# PCB_Telemetria_2020.net
KiCad netlist of a schematic drawn in EAGLE
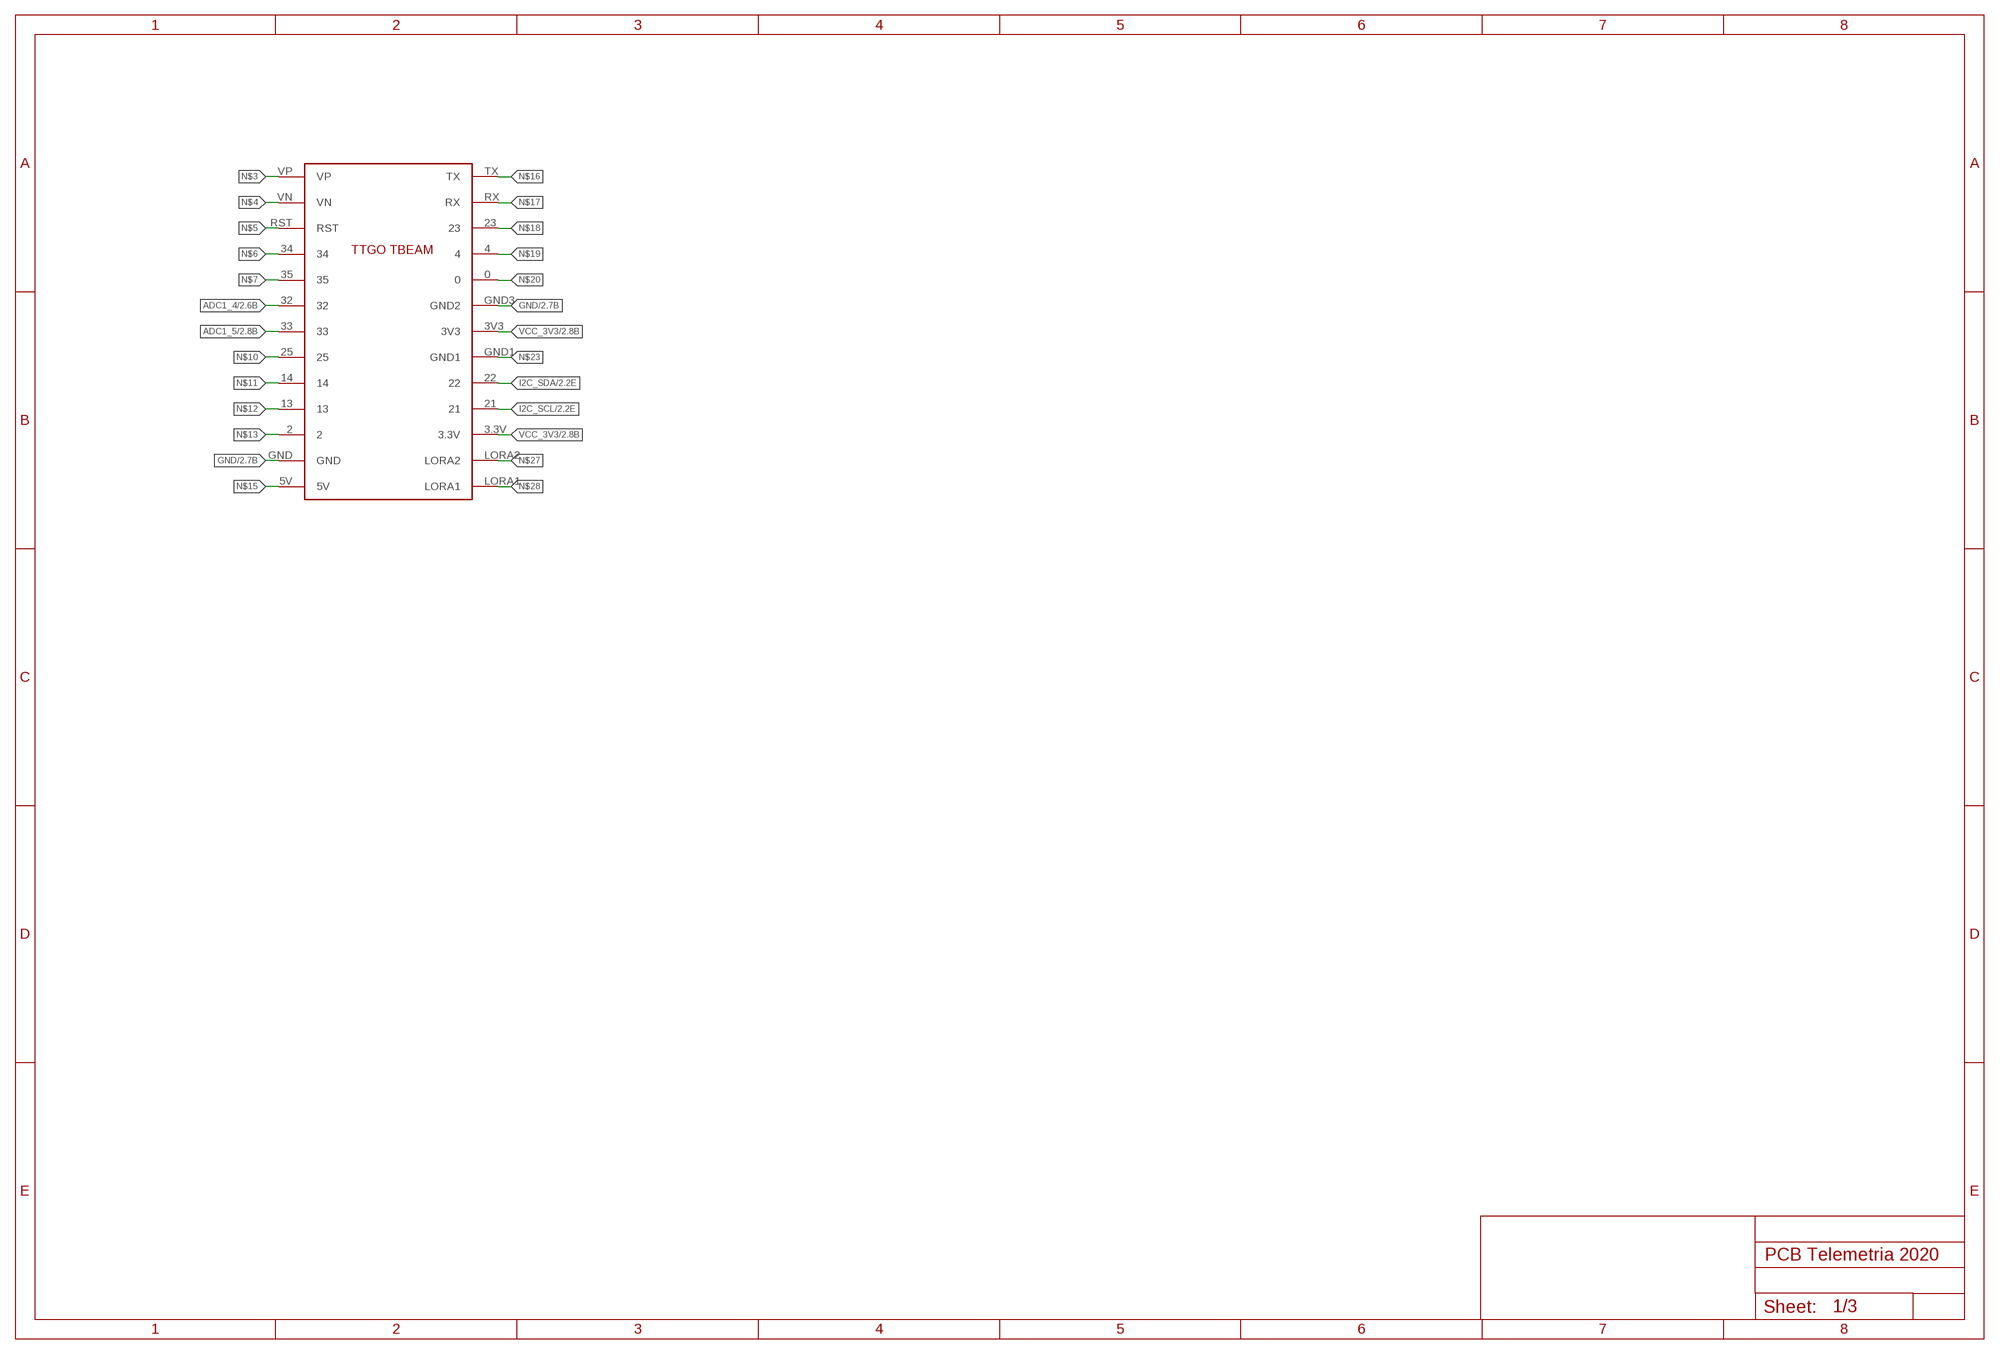
[diagram p0: schematic, sheet 1]
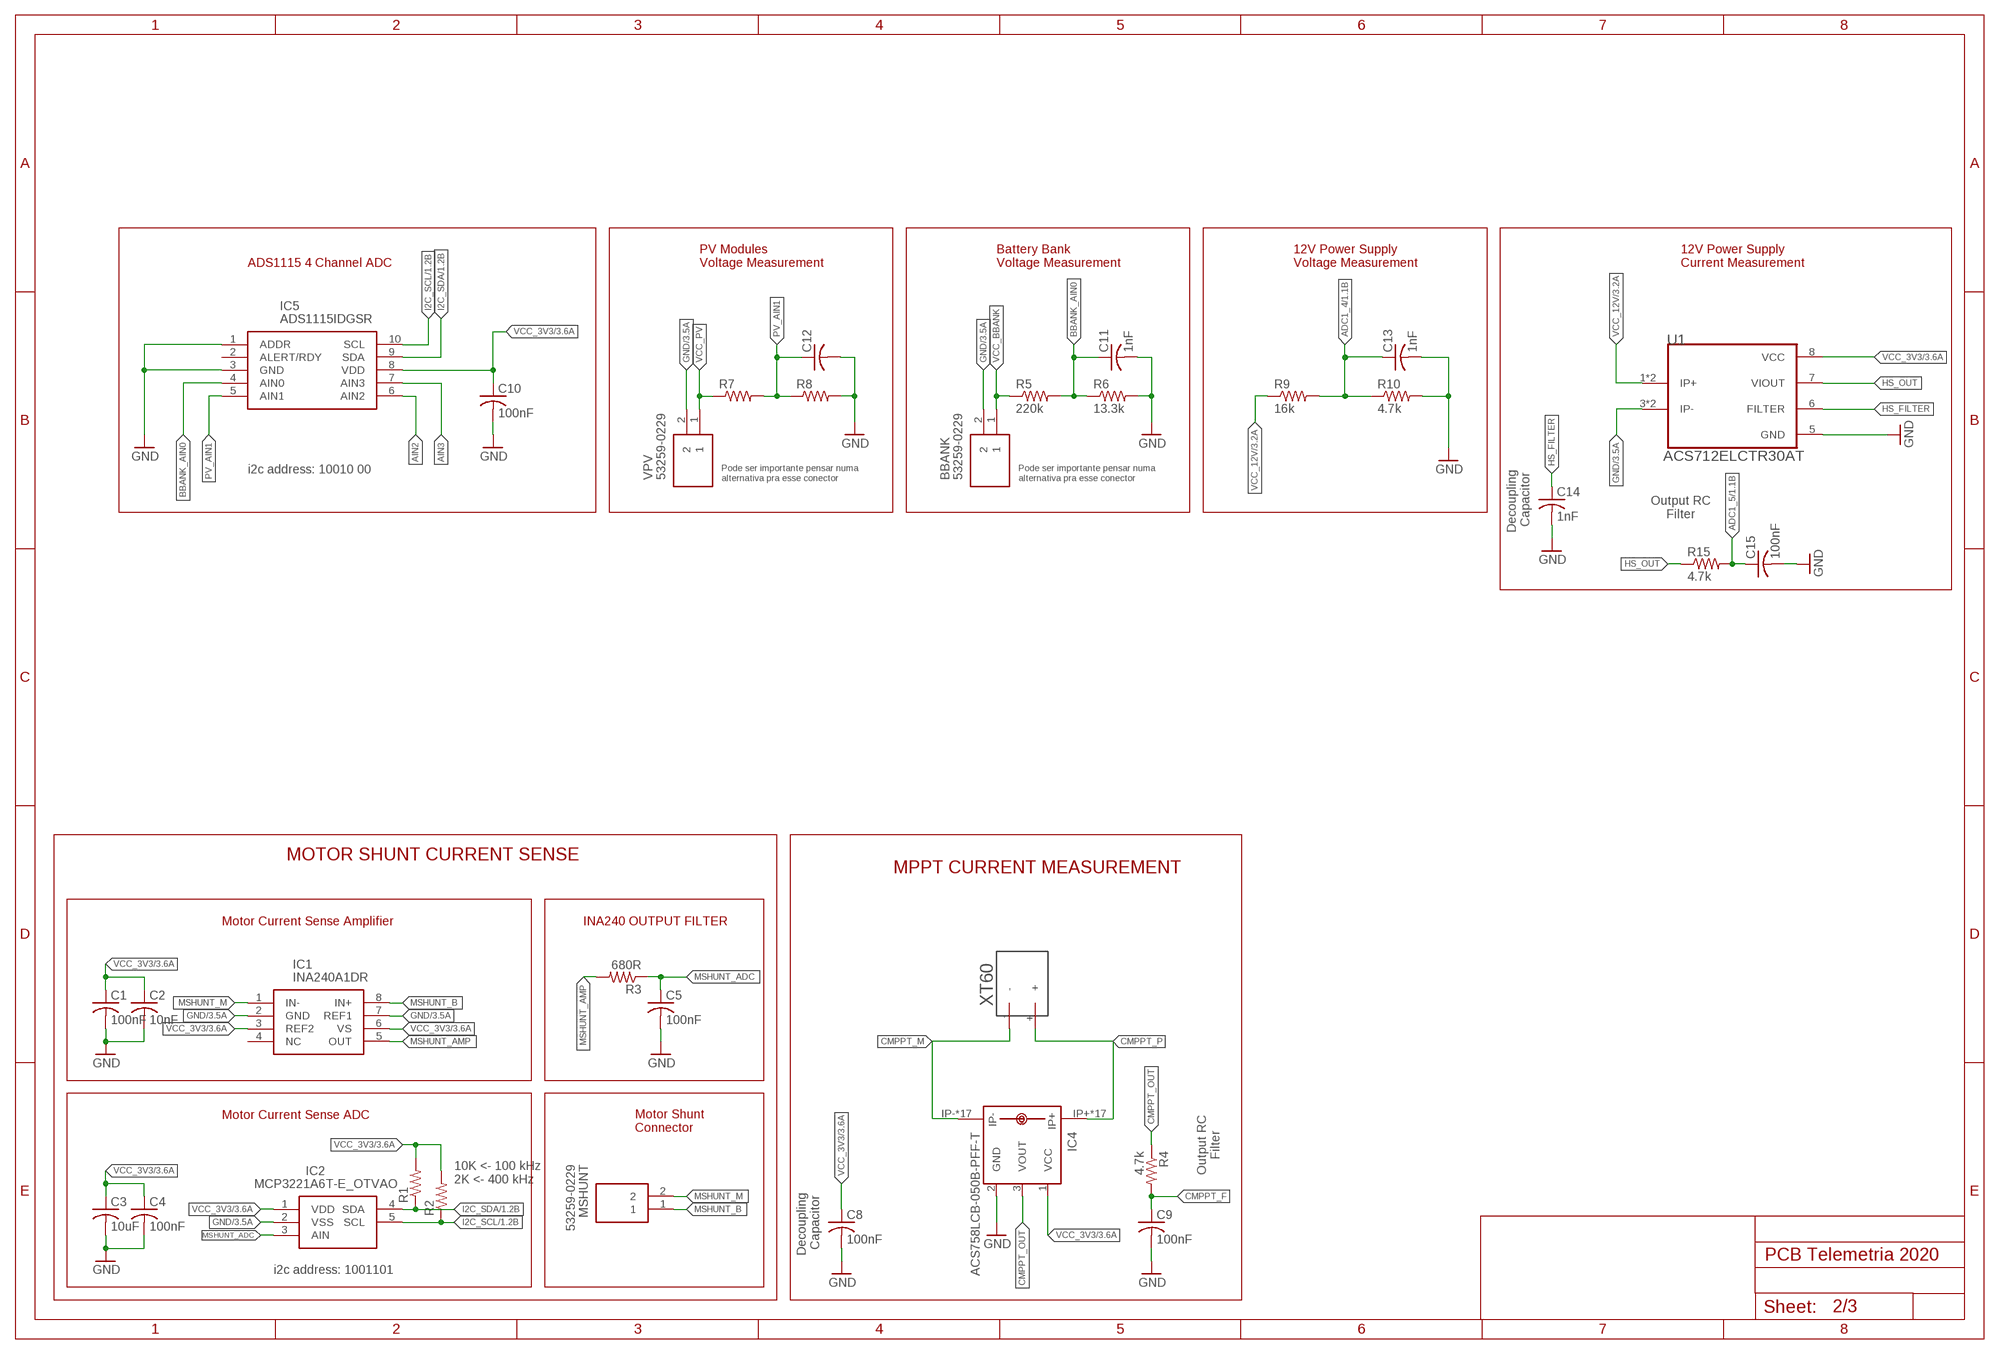
[diagram p1: schematic, sheet 2]
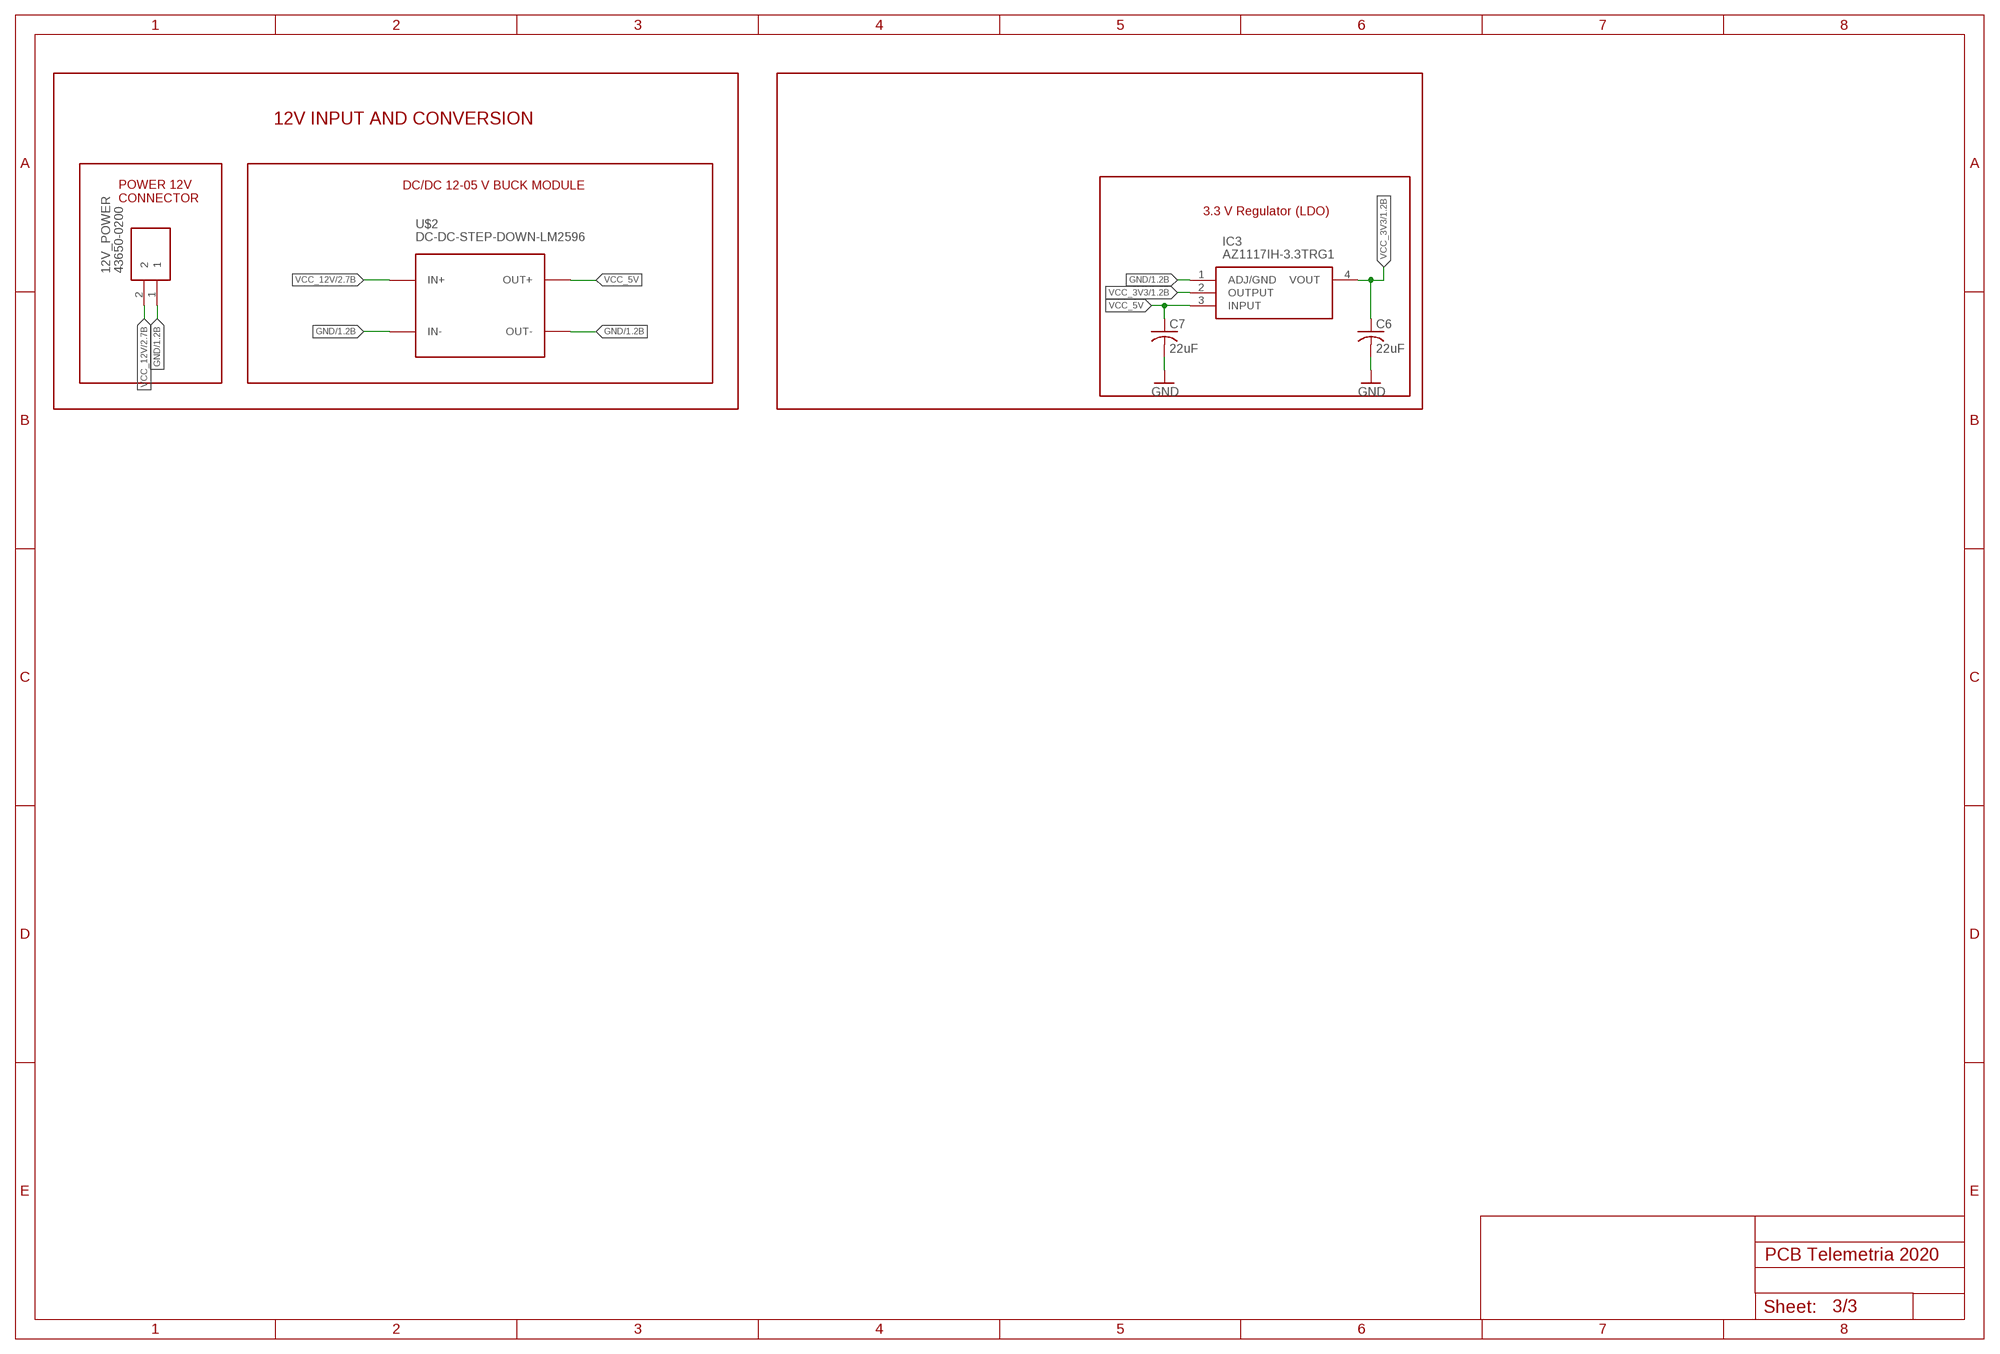
[diagram p2: schematic, sheet 3]

(export (version "E")
  (design (tool "Eeschema 10.0.6"))
  (components
    (comp (ref "12V_POWER")
      (value "43650-0200")
      (footprint "eagle-import:43650-0200")
      (fields (field (name "MOUSER_PART_NUMBER") "538-43650-0200"))
      (libsource (lib "eagle-import") (part "43650-0200"))
    )
    (comp (ref "C6")
      (value "22uF")
      (footprint "eagle-import:C0805")
      (libsource (lib "eagle-import") (part "C-USC0805"))
    )
    (comp (ref "C7")
      (value "22uF")
      (footprint "eagle-import:C0805")
      (libsource (lib "eagle-import") (part "C-USC0805"))
    )
    (comp (ref "IC3")
      (value "AZ1117IH-3.3TRG1")
      (footprint "eagle-import:SOT230P700X170-4N")
      (fields (field (name "MOUSER_PART_NUMBER") "621-AZ1117IH-3.3TRG1"))
      (libsource (lib "eagle-import") (part "AZ1117IH-3.3TRG1"))
    )
    (comp (ref "U$2")
      (value "DC-DC-STEP-DOWN-LM2596")
      (footprint "eagle-import:DC-DC-STEP-DOWN-LM2596")
      (libsource (lib "eagle-import") (part "DC-DC-STEP-DOWN-LM2596"))
    )
    (comp (ref "BBANK")
      (value "53259-0229")
      (footprint "eagle-import:0532590229")
      (fields (field (name "MOUSER_PART_NUMBER") "538-53259-0229"))
      (libsource (lib "eagle-import") (part "53259-0229"))
    )
    (comp (ref "C1")
      (value "100nF")
      (footprint "eagle-import:C0805")
      (libsource (lib "eagle-import") (part "C-USC0805"))
    )
    (comp (ref "C2")
      (value "10nF")
      (footprint "eagle-import:C0805")
      (libsource (lib "eagle-import") (part "C-USC0805"))
    )
    (comp (ref "C3")
      (value "10uF")
      (footprint "eagle-import:C0805")
      (libsource (lib "eagle-import") (part "C-USC0805"))
    )
    (comp (ref "C4")
      (value "100nF")
      (footprint "eagle-import:C0805")
      (libsource (lib "eagle-import") (part "C-USC0805"))
    )
    (comp (ref "C5")
      (value "100nF")
      (footprint "eagle-import:C0805")
      (libsource (lib "eagle-import") (part "C-USC0805"))
    )
    (comp (ref "C8")
      (value "100nF")
      (footprint "eagle-import:C0805")
      (libsource (lib "eagle-import") (part "C-USC0805"))
    )
    (comp (ref "C9")
      (value "100nF")
      (footprint "eagle-import:C0805")
      (libsource (lib "eagle-import") (part "C-USC0805"))
    )
    (comp (ref "C10")
      (value "100nF")
      (footprint "eagle-import:C0805")
      (libsource (lib "eagle-import") (part "C-USC0805"))
    )
    (comp (ref "C11")
      (value "1nF")
      (footprint "eagle-import:C0805")
      (libsource (lib "eagle-import") (part "C-USC0805"))
    )
    (comp (ref "C12")
      (value "C-USC0805")
      (footprint "eagle-import:C0805")
      (libsource (lib "eagle-import") (part "C-USC0805"))
    )
    (comp (ref "C13")
      (value "1nF")
      (footprint "eagle-import:C0805")
      (libsource (lib "eagle-import") (part "C-USC0805"))
    )
    (comp (ref "C14")
      (value "1nF")
      (footprint "eagle-import:C0805")
      (libsource (lib "eagle-import") (part "C-USC0805"))
    )
    (comp (ref "C15")
      (value "100nF")
      (footprint "eagle-import:C0805")
      (libsource (lib "eagle-import") (part "C-USC0805"))
    )
    (comp (ref "IC1")
      (value "INA240A1DR")
      (footprint "eagle-import:SOIC127P600X175-8N")
      (fields (field (name "MOUSER_PART_NUMBER") "595-INA240A1DR"))
      (libsource (lib "eagle-import") (part "INA240A1DR"))
    )
    (comp (ref "IC2")
      (value "MCP3221A6T-E_OTVAO")
      (footprint "eagle-import:SOT95P280X145-5N")
      (fields
        (field (name "MANUFACTURER_PART_NUMBER") "MCP3221A6T-E/OTVAO")
        (field (name "MOUSER_PART_NUMBER") "579-MCP3221A6TEOTVAO")
      )
      (libsource (lib "eagle-import") (part "MCP3221A6T-E_OTVAO"))
    )
    (comp (ref "IC4")
      (value "ACS758LCB-050B-PFF-T")
      (footprint "eagle-import:CB-PFF")
      (libsource (lib "eagle-import") (part "ACS758LCB-050B-PFF-T"))
    )
    (comp (ref "IC5")
      (value "ADS1115IDGSR")
      (footprint "eagle-import:SOP50P490X110-10N")
      (fields (field (name "MOUSER_PART_NUMBER") "595-ADS1115IDGSR"))
      (libsource (lib "eagle-import") (part "ADS1115IDGSR"))
    )
    (comp (ref "MSHUNT")
      (value "53259-0229")
      (footprint "eagle-import:0532590229")
      (fields (field (name "MOUSER_PART_NUMBER") "538-53259-0229"))
      (libsource (lib "eagle-import") (part "53259-0229"))
    )
    (comp (ref "R1")
      (value "R-US_R0805")
      (footprint "eagle-import:R0805")
      (libsource (lib "eagle-import") (part "R-US_R0805"))
    )
    (comp (ref "R2")
      (value "R-US_R0805")
      (footprint "eagle-import:R0805")
      (libsource (lib "eagle-import") (part "R-US_R0805"))
    )
    (comp (ref "R3")
      (value "680R")
      (footprint "eagle-import:R0805")
      (libsource (lib "eagle-import") (part "R-US_R0805"))
    )
    (comp (ref "R4")
      (value "4.7k")
      (footprint "eagle-import:R0805")
      (libsource (lib "eagle-import") (part "R-US_R0805"))
    )
    (comp (ref "R5")
      (value "220k")
      (footprint "eagle-import:R0805")
      (libsource (lib "eagle-import") (part "R-US_R0805"))
    )
    (comp (ref "R6")
      (value "13.3k")
      (footprint "eagle-import:R0805")
      (libsource (lib "eagle-import") (part "R-US_R0805"))
    )
    (comp (ref "R7")
      (value "R-US_R0805")
      (footprint "eagle-import:R0805")
      (libsource (lib "eagle-import") (part "R-US_R0805"))
    )
    (comp (ref "R8")
      (value "R-US_R0805")
      (footprint "eagle-import:R0805")
      (libsource (lib "eagle-import") (part "R-US_R0805"))
    )
    (comp (ref "R9")
      (value "16k")
      (footprint "eagle-import:R0805")
      (libsource (lib "eagle-import") (part "R-US_R0805"))
    )
    (comp (ref "R10")
      (value "4.7k")
      (footprint "eagle-import:R0805")
      (libsource (lib "eagle-import") (part "R-US_R0805"))
    )
    (comp (ref "R15")
      (value "4.7k")
      (footprint "eagle-import:R0805")
      (libsource (lib "eagle-import") (part "R-US_R0805"))
    )
    (comp (ref "U$3")
      (value "XT60")
      (footprint "eagle-import:XT60")
      (libsource (lib "eagle-import") (part "XT60"))
    )
    (comp (ref "U1")
      (value "ACS712ELCTR30AT")
      (footprint "eagle-import:SOIC127P600X175-8N")
      (fields (field (name "MF") "Allegro") (field (name "MP") "ACS712ELCTR-30A-T"))
      (libsource (lib "eagle-import") (part "ACS712ELCTR30AT"))
    )
    (comp (ref "VPV")
      (value "53259-0229")
      (footprint "eagle-import:0532590229")
      (fields (field (name "MOUSER_PART_NUMBER") "538-53259-0229"))
      (libsource (lib "eagle-import") (part "53259-0229"))
    )
    (comp (ref "U$1")
      (value "TTGOBEAM")
      (footprint "eagle-import:TTGOBEAM")
      (libsource (lib "eagle-import") (part "TTGOBEAM"))
    )
  )
  (nets
    (net (code "1") (name "ADC1_4") (class "Default")
      (node (ref "C13") (pin "1") (pinfunction "1_1") (pintype "passive"))
      (node (ref "R10") (pin "1") (pinfunction "1_1") (pintype "passive"))
      (node (ref "R9") (pin "2") (pinfunction "2_2") (pintype "passive"))
      (node (ref "U$1") (pin "32") (pinfunction "32_32") (pintype "bidirectional"))
    )
    (net (code "2") (name "ADC1_5") (class "Default")
      (node (ref "C15") (pin "1") (pinfunction "1_1") (pintype "passive"))
      (node (ref "R15") (pin "2") (pinfunction "2_2") (pintype "passive"))
      (node (ref "U$1") (pin "33") (pinfunction "33_33") (pintype "bidirectional"))
    )
    (net (code "3") (name "AIN2") (class "Default")
      (node (ref "IC5") (pin "6") (pinfunction "AIN2_6") (pintype "bidirectional"))
    )
    (net (code "4") (name "AIN3") (class "Default")
      (node (ref "IC5") (pin "7") (pinfunction "AIN3_7") (pintype "bidirectional"))
    )
    (net (code "5") (name "BBANK_AIN0") (class "Default")
      (node (ref "C11") (pin "1") (pinfunction "1_1") (pintype "passive"))
      (node (ref "IC5") (pin "4") (pinfunction "AIN0_4") (pintype "bidirectional"))
      (node (ref "R5") (pin "2") (pinfunction "2_2") (pintype "passive"))
      (node (ref "R6") (pin "1") (pinfunction "1_1") (pintype "passive"))
    )
    (net (code "6") (name "CMPPT_F") (class "Default")
      (node (ref "C9") (pin "1") (pinfunction "1_1") (pintype "passive"))
      (node (ref "R4") (pin "2") (pinfunction "2_2") (pintype "passive"))
    )
    (net (code "7") (name "CMPPT_M") (class "Default")
      (node (ref "IC4") (pin "IP-") (pinfunction "IP-_IP-") (pintype "passive"))
      (node (ref "IC4") (pin "IP-@10") (pinfunction "IP-_IP-@10") (pintype "passive"))
      (node (ref "IC4") (pin "IP-@11") (pinfunction "IP-_IP-@11") (pintype "passive"))
      (node (ref "IC4") (pin "IP-@12") (pinfunction "IP-_IP-@12") (pintype "passive"))
      (node (ref "IC4") (pin "IP-@13") (pinfunction "IP-_IP-@13") (pintype "passive"))
      (node (ref "IC4") (pin "IP-@14") (pinfunction "IP-_IP-@14") (pintype "passive"))
      (node (ref "IC4") (pin "IP-@15") (pinfunction "IP-_IP-@15") (pintype "passive"))
      (node (ref "IC4") (pin "IP-@16") (pinfunction "IP-_IP-@16") (pintype "passive"))
      (node (ref "IC4") (pin "IP-@17") (pinfunction "IP-_IP-@17") (pintype "passive"))
      (node (ref "IC4") (pin "IP-@2") (pinfunction "IP-_IP-@2") (pintype "passive"))
      (node (ref "IC4") (pin "IP-@3") (pinfunction "IP-_IP-@3") (pintype "passive"))
      (node (ref "IC4") (pin "IP-@4") (pinfunction "IP-_IP-@4") (pintype "passive"))
      (node (ref "IC4") (pin "IP-@5") (pinfunction "IP-_IP-@5") (pintype "passive"))
      (node (ref "IC4") (pin "IP-@6") (pinfunction "IP-_IP-@6") (pintype "passive"))
      (node (ref "IC4") (pin "IP-@7") (pinfunction "IP-_IP-@7") (pintype "passive"))
      (node (ref "IC4") (pin "IP-@8") (pinfunction "IP-_IP-@8") (pintype "passive"))
      (node (ref "IC4") (pin "IP-@9") (pinfunction "IP-_IP-@9") (pintype "passive"))
      (node (ref "U$3") (pin "-") (pinfunction "-_-") (pintype "bidirectional"))
    )
    (net (code "8") (name "CMPPT_OUT") (class "Default")
      (node (ref "IC4") (pin "3") (pinfunction "VOUT_3") (pintype "output"))
      (node (ref "R4") (pin "1") (pinfunction "1_1") (pintype "passive"))
    )
    (net (code "9") (name "CMPPT_P") (class "Default")
      (node (ref "IC4") (pin "IP+") (pinfunction "IP+_IP+") (pintype "passive"))
      (node (ref "IC4") (pin "IP+@10") (pinfunction "IP+_IP+@10") (pintype "passive"))
      (node (ref "IC4") (pin "IP+@11") (pinfunction "IP+_IP+@11") (pintype "passive"))
      (node (ref "IC4") (pin "IP+@12") (pinfunction "IP+_IP+@12") (pintype "passive"))
      (node (ref "IC4") (pin "IP+@13") (pinfunction "IP+_IP+@13") (pintype "passive"))
      (node (ref "IC4") (pin "IP+@14") (pinfunction "IP+_IP+@14") (pintype "passive"))
      (node (ref "IC4") (pin "IP+@15") (pinfunction "IP+_IP+@15") (pintype "passive"))
      (node (ref "IC4") (pin "IP+@16") (pinfunction "IP+_IP+@16") (pintype "passive"))
      (node (ref "IC4") (pin "IP+@17") (pinfunction "IP+_IP+@17") (pintype "passive"))
      (node (ref "IC4") (pin "IP+@2") (pinfunction "IP+_IP+@2") (pintype "passive"))
      (node (ref "IC4") (pin "IP+@3") (pinfunction "IP+_IP+@3") (pintype "passive"))
      (node (ref "IC4") (pin "IP+@4") (pinfunction "IP+_IP+@4") (pintype "passive"))
      (node (ref "IC4") (pin "IP+@5") (pinfunction "IP+_IP+@5") (pintype "passive"))
      (node (ref "IC4") (pin "IP+@6") (pinfunction "IP+_IP+@6") (pintype "passive"))
      (node (ref "IC4") (pin "IP+@7") (pinfunction "IP+_IP+@7") (pintype "passive"))
      (node (ref "IC4") (pin "IP+@8") (pinfunction "IP+_IP+@8") (pintype "passive"))
      (node (ref "IC4") (pin "IP+@9") (pinfunction "IP+_IP+@9") (pintype "passive"))
      (node (ref "U$3") (pin "+") (pinfunction "+_+") (pintype "bidirectional"))
    )
    (net (code "10") (name "GND") (class "Default")
      (node (ref "12V_POWER") (pin "1") (pinfunction "1_1") (pintype "bidirectional"))
      (node (ref "BBANK") (pin "2") (pinfunction "2_2") (pintype "bidirectional"))
      (node (ref "C1") (pin "2") (pinfunction "2_2") (pintype "passive"))
      (node (ref "C10") (pin "2") (pinfunction "2_2") (pintype "passive"))
      (node (ref "C11") (pin "2") (pinfunction "2_2") (pintype "passive"))
      (node (ref "C12") (pin "2") (pinfunction "2_2") (pintype "passive"))
      (node (ref "C13") (pin "2") (pinfunction "2_2") (pintype "passive"))
      (node (ref "C14") (pin "2") (pinfunction "2_2") (pintype "passive"))
      (node (ref "C15") (pin "2") (pinfunction "2_2") (pintype "passive"))
      (node (ref "C2") (pin "2") (pinfunction "2_2") (pintype "passive"))
      (node (ref "C3") (pin "2") (pinfunction "2_2") (pintype "passive"))
      (node (ref "C4") (pin "2") (pinfunction "2_2") (pintype "passive"))
      (node (ref "C5") (pin "2") (pinfunction "2_2") (pintype "passive"))
      (node (ref "C6") (pin "2") (pinfunction "2_2") (pintype "passive"))
      (node (ref "C7") (pin "2") (pinfunction "2_2") (pintype "passive"))
      (node (ref "C8") (pin "2") (pinfunction "2_2") (pintype "passive"))
      (node (ref "C9") (pin "2") (pinfunction "2_2") (pintype "passive"))
      (node (ref "IC1") (pin "2") (pinfunction "GND_2") (pintype "bidirectional"))
      (node (ref "IC1") (pin "7") (pinfunction "REF1_7") (pintype "bidirectional"))
      (node (ref "IC2") (pin "2") (pinfunction "VSS_2") (pintype "bidirectional"))
      (node (ref "IC3") (pin "1") (pinfunction "ADJ/GND_1") (pintype "bidirectional"))
      (node (ref "IC4") (pin "2") (pinfunction "GND_2") (pintype "power_in"))
      (node (ref "IC5") (pin "1") (pinfunction "ADDR_1") (pintype "bidirectional"))
      (node (ref "IC5") (pin "3") (pinfunction "GND_3") (pintype "bidirectional"))
      (node (ref "R10") (pin "2") (pinfunction "2_2") (pintype "passive"))
      (node (ref "R6") (pin "2") (pinfunction "2_2") (pintype "passive"))
      (node (ref "R8") (pin "2") (pinfunction "2_2") (pintype "passive"))
      (node (ref "U$1") (pin "GND") (pinfunction "GND_GND") (pintype "bidirectional"))
      (node (ref "U$1") (pin "GND3") (pinfunction "GND2_GND3") (pintype "bidirectional"))
      (node (ref "U$2") (pin "IN-") (pinfunction "IN-_IN-") (pintype "bidirectional"))
      (node (ref "U$2") (pin "OUT-") (pinfunction "OUT-_OUT-") (pintype "bidirectional"))
      (node (ref "U1") (pin "3") (pinfunction "IP-_3") (pintype "input"))
      (node (ref "U1") (pin "4") (pinfunction "IP-_4") (pintype "input"))
      (node (ref "U1") (pin "5") (pinfunction "GND_5") (pintype "power_in"))
      (node (ref "VPV") (pin "2") (pinfunction "2_2") (pintype "bidirectional"))
    )
    (net (code "11") (name "HS_FILTER") (class "Default")
      (node (ref "C14") (pin "1") (pinfunction "1_1") (pintype "passive"))
      (node (ref "U1") (pin "6") (pinfunction "FILTER_6") (pintype "passive"))
    )
    (net (code "12") (name "HS_OUT") (class "Default")
      (node (ref "R15") (pin "1") (pinfunction "1_1") (pintype "passive"))
      (node (ref "U1") (pin "7") (pinfunction "VIOUT_7") (pintype "output"))
    )
    (net (code "13") (name "I2C_SCL") (class "Default")
      (node (ref "IC2") (pin "5") (pinfunction "SCL_5") (pintype "bidirectional"))
      (node (ref "IC5") (pin "10") (pinfunction "SCL_10") (pintype "bidirectional"))
      (node (ref "R2") (pin "1") (pinfunction "1_1") (pintype "passive"))
      (node (ref "U$1") (pin "21") (pinfunction "21_21") (pintype "bidirectional"))
    )
    (net (code "14") (name "I2C_SDA") (class "Default")
      (node (ref "IC2") (pin "4") (pinfunction "SDA_4") (pintype "bidirectional"))
      (node (ref "IC5") (pin "9") (pinfunction "SDA_9") (pintype "bidirectional"))
      (node (ref "R1") (pin "1") (pinfunction "1_1") (pintype "passive"))
      (node (ref "U$1") (pin "22") (pinfunction "22_22") (pintype "bidirectional"))
    )
    (net (code "15") (name "MSHUNT_ADC") (class "Default")
      (node (ref "C5") (pin "1") (pinfunction "1_1") (pintype "passive"))
      (node (ref "IC2") (pin "3") (pinfunction "AIN_3") (pintype "bidirectional"))
      (node (ref "R3") (pin "1") (pinfunction "1_1") (pintype "passive"))
    )
    (net (code "16") (name "MSHUNT_AMP") (class "Default")
      (node (ref "IC1") (pin "5") (pinfunction "OUT_5") (pintype "bidirectional"))
      (node (ref "R3") (pin "2") (pinfunction "2_2") (pintype "passive"))
    )
    (net (code "17") (name "MSHUNT_B") (class "Default")
      (node (ref "IC1") (pin "8") (pinfunction "IN+_8") (pintype "bidirectional"))
      (node (ref "MSHUNT") (pin "1") (pinfunction "1_1") (pintype "bidirectional"))
    )
    (net (code "18") (name "MSHUNT_M") (class "Default")
      (node (ref "IC1") (pin "1") (pinfunction "IN-_1") (pintype "bidirectional"))
      (node (ref "MSHUNT") (pin "2") (pinfunction "2_2") (pintype "bidirectional"))
    )
    (net (code "19") (name "N$3") (class "Default")
      (node (ref "U$1") (pin "VP") (pinfunction "VP_VP") (pintype "bidirectional"))
    )
    (net (code "20") (name "N$4") (class "Default")
      (node (ref "U$1") (pin "VN") (pinfunction "VN_VN") (pintype "bidirectional"))
    )
    (net (code "21") (name "N$5") (class "Default")
      (node (ref "U$1") (pin "RST") (pinfunction "RST_RST") (pintype "bidirectional"))
    )
    (net (code "22") (name "N$6") (class "Default")
      (node (ref "U$1") (pin "34") (pinfunction "34_34") (pintype "bidirectional"))
    )
    (net (code "23") (name "N$7") (class "Default")
      (node (ref "U$1") (pin "35") (pinfunction "35_35") (pintype "bidirectional"))
    )
    (net (code "24") (name "N$10") (class "Default")
      (node (ref "U$1") (pin "25") (pinfunction "25_25") (pintype "bidirectional"))
    )
    (net (code "25") (name "N$11") (class "Default")
      (node (ref "U$1") (pin "14") (pinfunction "14_14") (pintype "bidirectional"))
    )
    (net (code "26") (name "N$12") (class "Default")
      (node (ref "U$1") (pin "13") (pinfunction "13_13") (pintype "bidirectional"))
    )
    (net (code "27") (name "N$13") (class "Default")
      (node (ref "U$1") (pin "2") (pinfunction "2_2") (pintype "bidirectional"))
    )
    (net (code "28") (name "N$15") (class "Default")
      (node (ref "U$1") (pin "5V") (pinfunction "5V_5V") (pintype "bidirectional"))
    )
    (net (code "29") (name "N$16") (class "Default")
      (node (ref "U$1") (pin "TX") (pinfunction "TX_TX") (pintype "bidirectional"))
    )
    (net (code "30") (name "N$17") (class "Default")
      (node (ref "U$1") (pin "RX") (pinfunction "RX_RX") (pintype "bidirectional"))
    )
    (net (code "31") (name "N$18") (class "Default")
      (node (ref "U$1") (pin "23") (pinfunction "23_23") (pintype "bidirectional"))
    )
    (net (code "32") (name "N$19") (class "Default")
      (node (ref "U$1") (pin "4") (pinfunction "4_4") (pintype "bidirectional"))
    )
    (net (code "33") (name "N$20") (class "Default")
      (node (ref "U$1") (pin "0") (pinfunction "0_0") (pintype "bidirectional"))
    )
    (net (code "34") (name "N$23") (class "Default")
      (node (ref "U$1") (pin "GND1") (pinfunction "GND1_GND1") (pintype "bidirectional"))
    )
    (net (code "35") (name "N$27") (class "Default")
      (node (ref "U$1") (pin "LORA2") (pinfunction "LORA2_LORA2") (pintype "bidirectional"))
    )
    (net (code "36") (name "N$28") (class "Default")
      (node (ref "U$1") (pin "LORA1") (pinfunction "LORA1_LORA1") (pintype "bidirectional"))
    )
    (net (code "37") (name "PV_AIN1") (class "Default")
      (node (ref "C12") (pin "1") (pinfunction "1_1") (pintype "passive"))
      (node (ref "IC5") (pin "5") (pinfunction "AIN1_5") (pintype "bidirectional"))
      (node (ref "R7") (pin "2") (pinfunction "2_2") (pintype "passive"))
      (node (ref "R8") (pin "1") (pinfunction "1_1") (pintype "passive"))
    )
    (net (code "38") (name "VCC_3V3") (class "Default")
      (node (ref "C1") (pin "1") (pinfunction "1_1") (pintype "passive"))
      (node (ref "C10") (pin "1") (pinfunction "1_1") (pintype "passive"))
      (node (ref "C2") (pin "1") (pinfunction "1_1") (pintype "passive"))
      (node (ref "C3") (pin "1") (pinfunction "1_1") (pintype "passive"))
      (node (ref "C4") (pin "1") (pinfunction "1_1") (pintype "passive"))
      (node (ref "C6") (pin "1") (pinfunction "1_1") (pintype "passive"))
      (node (ref "C8") (pin "1") (pinfunction "1_1") (pintype "passive"))
      (node (ref "IC1") (pin "3") (pinfunction "REF2_3") (pintype "bidirectional"))
      (node (ref "IC1") (pin "6") (pinfunction "VS_6") (pintype "bidirectional"))
      (node (ref "IC2") (pin "1") (pinfunction "VDD_1") (pintype "bidirectional"))
      (node (ref "IC3") (pin "2") (pinfunction "OUTPUT_2") (pintype "bidirectional"))
      (node (ref "IC3") (pin "4") (pinfunction "VOUT_4") (pintype "bidirectional"))
      (node (ref "IC4") (pin "1") (pinfunction "VCC_1") (pintype "power_in"))
      (node (ref "IC5") (pin "8") (pinfunction "VDD_8") (pintype "bidirectional"))
      (node (ref "R1") (pin "2") (pinfunction "2_2") (pintype "passive"))
      (node (ref "R2") (pin "2") (pinfunction "2_2") (pintype "passive"))
      (node (ref "U$1") (pin "3.3V") (pinfunction "3.3V_3.3V") (pintype "bidirectional"))
      (node (ref "U$1") (pin "3V3") (pinfunction "3V3_3V3") (pintype "bidirectional"))
      (node (ref "U1") (pin "8") (pinfunction "VCC_8") (pintype "power_in"))
    )
    (net (code "39") (name "VCC_5V") (class "Default")
      (node (ref "C7") (pin "1") (pinfunction "1_1") (pintype "passive"))
      (node (ref "IC3") (pin "3") (pinfunction "INPUT_3") (pintype "bidirectional"))
      (node (ref "U$2") (pin "OUT+") (pinfunction "OUT+_OUT+") (pintype "bidirectional"))
    )
    (net (code "40") (name "VCC_12V") (class "Default")
      (node (ref "12V_POWER") (pin "2") (pinfunction "2_2") (pintype "bidirectional"))
      (node (ref "R9") (pin "1") (pinfunction "1_1") (pintype "passive"))
      (node (ref "U$2") (pin "IN+") (pinfunction "IN+_IN+") (pintype "bidirectional"))
      (node (ref "U1") (pin "1") (pinfunction "IP+_1") (pintype "input"))
      (node (ref "U1") (pin "2") (pinfunction "IP+_2") (pintype "input"))
    )
    (net (code "41") (name "VCC_BBANK") (class "Default")
      (node (ref "BBANK") (pin "1") (pinfunction "1_1") (pintype "bidirectional"))
      (node (ref "R5") (pin "1") (pinfunction "1_1") (pintype "passive"))
    )
    (net (code "42") (name "VCC_PV") (class "Default")
      (node (ref "R7") (pin "1") (pinfunction "1_1") (pintype "passive"))
      (node (ref "VPV") (pin "1") (pinfunction "1_1") (pintype "bidirectional"))
    )
    (net (code "43") (name "unconnected-(IC1-NC-Pad4)") (class "Default")
      (node (ref "IC1") (pin "4") (pinfunction "NC_4") (pintype "no_connect"))
    )
    (net (code "44") (name "unconnected-(IC5-ALERT{slash}RDY-Pad2)") (class "Default")
      (node (ref "IC5") (pin "2") (pinfunction "ALERT/RDY_2") (pintype "bidirectional"))
    )
  )
)
